# pm25.net
KiCad netlist of a schematic drawn in EAGLE
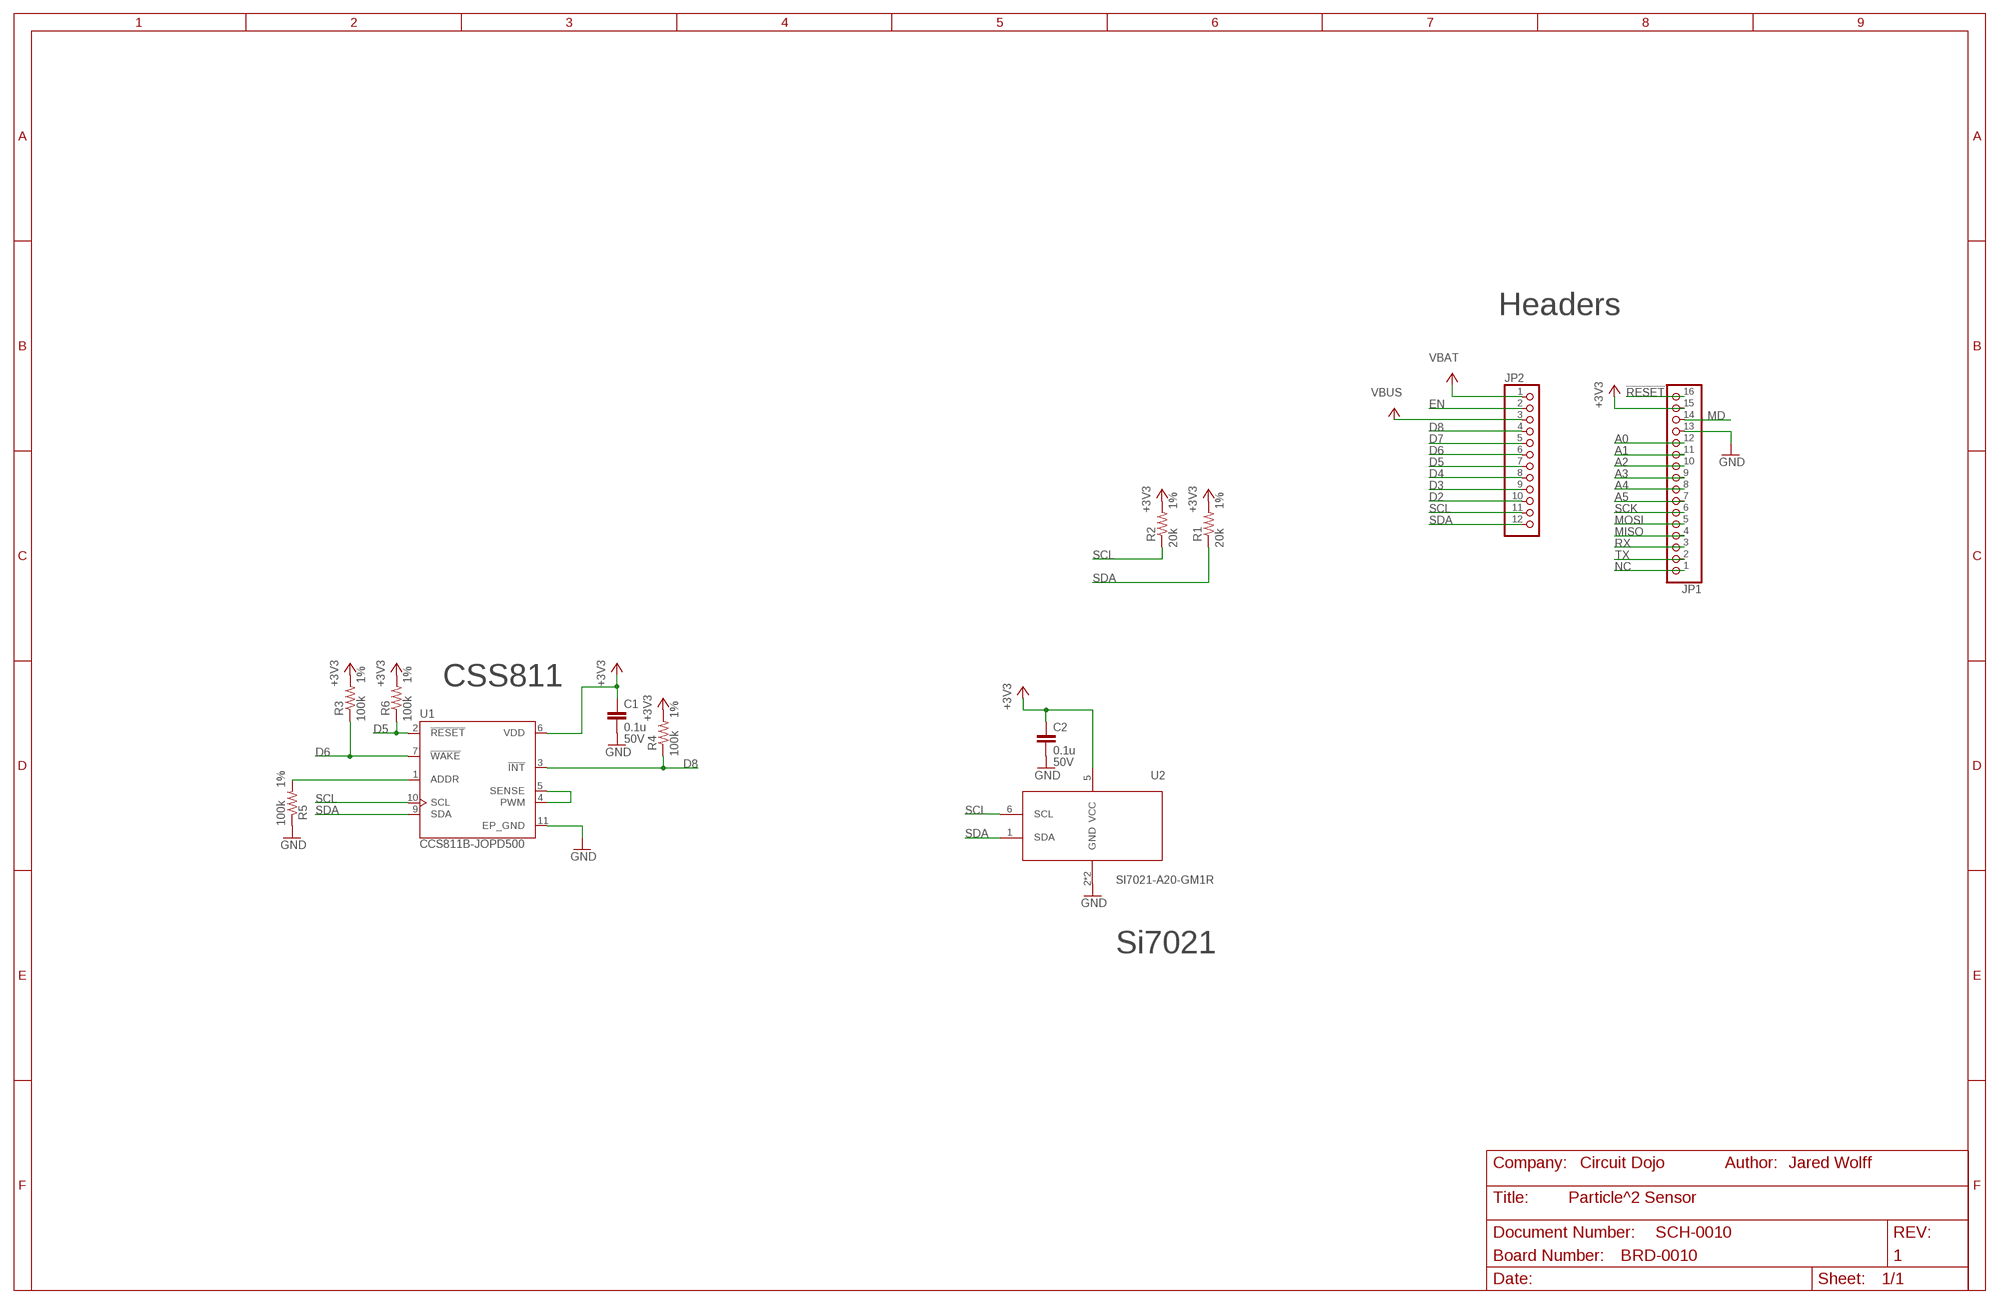
[diagram p0: schematic, sheet 1]

(export (version "E")
  (design (tool "Eeschema 10.0.6"))
  (components
    (comp (ref "C1")
      (value "0.1u")
      (footprint "eagle-import:CAPC1005X55N")
      (fields
        (field (name "VOLTHIGH") "50V")
        (field (name "MF") "Taiyo Yuden")
        (field (name "MPN") "UMK105BJ104KV-F")
      )
      (libsource (lib "eagle-import") (part "CAP-0017"))
    )
    (comp (ref "C2")
      (value "0.1u")
      (footprint "eagle-import:CAPC1005X55N")
      (fields
        (field (name "VOLTHIGH") "50V")
        (field (name "MF") "Taiyo Yuden")
        (field (name "MPN") "UMK105BJ104KV-F")
      )
      (libsource (lib "eagle-import") (part "CAP-0017"))
    )
    (comp (ref "JP1")
      (value "HEADER-1X16ROUND")
      (footprint "eagle-import:1X16_ROUND")
      (fields (field (name "MPN") "PPPC161LFBN-RC"))
      (libsource (lib "eagle-import") (part "HEADER-1X16ROUND"))
    )
    (comp (ref "JP2")
      (value "HEADER-1X12")
      (footprint "eagle-import:1X12_ROUND")
      (fields (field (name "MPN") "PPPC121LFBN-RC"))
      (libsource (lib "eagle-import") (part "HEADER-1X12"))
    )
    (comp (ref "R1")
      (value "20k")
      (footprint "eagle-import:R0402")
      (fields (field (name "TOLERANCE") "1%") (field (name "MPN") "RC0402FR-0720KL"))
      (libsource (lib "eagle-import") (part "RES-0054"))
    )
    (comp (ref "R2")
      (value "20k")
      (footprint "eagle-import:R0402")
      (fields (field (name "TOLERANCE") "1%") (field (name "MPN") "RC0402FR-0720KL"))
      (libsource (lib "eagle-import") (part "RES-0054"))
    )
    (comp (ref "R3")
      (value "100k")
      (footprint "eagle-import:R0402")
      (fields (field (name "TOLERANCE") "1%") (field (name "MPN") "RC0402FR07100KL"))
      (libsource (lib "eagle-import") (part "RES-0041"))
    )
    (comp (ref "R4")
      (value "100k")
      (footprint "eagle-import:R0402")
      (fields (field (name "TOLERANCE") "1%") (field (name "MPN") "RC0402FR07100KL"))
      (libsource (lib "eagle-import") (part "RES-0041"))
    )
    (comp (ref "R5")
      (value "100k")
      (footprint "eagle-import:R0402")
      (fields (field (name "TOLERANCE") "1%") (field (name "MPN") "RC0402FR07100KL"))
      (libsource (lib "eagle-import") (part "RES-0041"))
    )
    (comp (ref "R6")
      (value "100k")
      (footprint "eagle-import:R0402")
      (fields (field (name "TOLERANCE") "1%") (field (name "MPN") "RC0402FR07100KL"))
      (libsource (lib "eagle-import") (part "RES-0041"))
    )
    (comp (ref "U1")
      (value "CCS811B-JOPD500")
      (footprint "eagle-import:SON60P400X270X110-11N")
      (fields (field (name "MF") "ams"))
      (libsource (lib "eagle-import") (part "CCS811B-JOPD500"))
    )
    (comp (ref "U2")
      (value "SI7021-A20-GM1R")
      (footprint "eagle-import:SON100P300X300X80-7N")
      (fields (field (name "MPN") "SI7021-A20-GM1R"))
      (libsource (lib "eagle-import") (part "SI7021-A20-GM1R"))
    )
  )
  (nets
    (net (code "1") (name "+3V3") (class "Default")
      (node (ref "C1") (pin "1") (pinfunction "1_1") (pintype "passive"))
      (node (ref "C2") (pin "1") (pinfunction "1_1") (pintype "passive"))
      (node (ref "JP1") (pin "15") (pinfunction "15_15") (pintype "passive"))
      (node (ref "R1") (pin "2") (pinfunction "2_2") (pintype "passive"))
      (node (ref "R2") (pin "2") (pinfunction "2_2") (pintype "passive"))
      (node (ref "R3") (pin "2") (pinfunction "2_2") (pintype "passive"))
      (node (ref "R4") (pin "2") (pinfunction "2_2") (pintype "passive"))
      (node (ref "R6") (pin "2") (pinfunction "2_2") (pintype "passive"))
      (node (ref "U1") (pin "6") (pinfunction "VDD_6") (pintype "power_in"))
      (node (ref "U2") (pin "5") (pinfunction "VCC_5") (pintype "bidirectional"))
    )
    (net (code "2") (name "/A0") (class "Default")
      (node (ref "JP1") (pin "12") (pinfunction "12_12") (pintype "passive"))
    )
    (net (code "3") (name "/A1") (class "Default")
      (node (ref "JP1") (pin "11") (pinfunction "11_11") (pintype "passive"))
    )
    (net (code "4") (name "/A2") (class "Default")
      (node (ref "JP1") (pin "10") (pinfunction "10_10") (pintype "passive"))
    )
    (net (code "5") (name "/A3") (class "Default")
      (node (ref "JP1") (pin "9") (pinfunction "9_9") (pintype "passive"))
    )
    (net (code "6") (name "/A4") (class "Default")
      (node (ref "JP1") (pin "8") (pinfunction "8_8") (pintype "passive"))
    )
    (net (code "7") (name "/A5") (class "Default")
      (node (ref "JP1") (pin "7") (pinfunction "7_7") (pintype "passive"))
    )
    (net (code "8") (name "/D2") (class "Default")
      (node (ref "JP2") (pin "10") (pinfunction "10_10") (pintype "passive"))
    )
    (net (code "9") (name "/D3") (class "Default")
      (node (ref "JP2") (pin "9") (pinfunction "9_9") (pintype "passive"))
    )
    (net (code "10") (name "/D4") (class "Default")
      (node (ref "JP2") (pin "8") (pinfunction "8_8") (pintype "passive"))
    )
    (net (code "11") (name "/D5") (class "Default")
      (node (ref "JP2") (pin "7") (pinfunction "7_7") (pintype "passive"))
      (node (ref "R6") (pin "1") (pinfunction "1_1") (pintype "passive"))
      (node (ref "U1") (pin "2") (pinfunction "~{RESET}_2") (pintype "input"))
    )
    (net (code "12") (name "/D6") (class "Default")
      (node (ref "JP2") (pin "6") (pinfunction "6_6") (pintype "passive"))
      (node (ref "R3") (pin "1") (pinfunction "1_1") (pintype "passive"))
      (node (ref "U1") (pin "7") (pinfunction "~{WAKE}_7") (pintype "input"))
    )
    (net (code "13") (name "/D7") (class "Default")
      (node (ref "JP2") (pin "5") (pinfunction "5_5") (pintype "passive"))
    )
    (net (code "14") (name "/D8") (class "Default")
      (node (ref "JP2") (pin "4") (pinfunction "4_4") (pintype "passive"))
      (node (ref "R4") (pin "1") (pinfunction "1_1") (pintype "passive"))
      (node (ref "U1") (pin "3") (pinfunction "~{INT}_3") (pintype "output"))
    )
    (net (code "15") (name "/EN") (class "Default")
      (node (ref "JP2") (pin "2") (pinfunction "2_2") (pintype "passive"))
    )
    (net (code "16") (name "/MD") (class "Default")
      (node (ref "JP1") (pin "14") (pinfunction "14_14") (pintype "passive"))
    )
    (net (code "17") (name "/MISO") (class "Default")
      (node (ref "JP1") (pin "4") (pinfunction "4_4") (pintype "passive"))
    )
    (net (code "18") (name "/MOSI") (class "Default")
      (node (ref "JP1") (pin "5") (pinfunction "5_5") (pintype "passive"))
    )
    (net (code "19") (name "/NC") (class "Default")
      (node (ref "JP1") (pin "1") (pinfunction "1_1") (pintype "passive"))
    )
    (net (code "20") (name "/RX") (class "Default")
      (node (ref "JP1") (pin "3") (pinfunction "3_3") (pintype "passive"))
    )
    (net (code "21") (name "/SCK") (class "Default")
      (node (ref "JP1") (pin "6") (pinfunction "6_6") (pintype "passive"))
    )
    (net (code "22") (name "/SCL") (class "Default")
      (node (ref "JP2") (pin "11") (pinfunction "11_11") (pintype "passive"))
      (node (ref "R2") (pin "1") (pinfunction "1_1") (pintype "passive"))
      (node (ref "U1") (pin "10") (pinfunction "SCL_10") (pintype "input"))
      (node (ref "U2") (pin "6") (pinfunction "SCL_6") (pintype "bidirectional"))
    )
    (net (code "23") (name "/SDA") (class "Default")
      (node (ref "JP2") (pin "12") (pinfunction "12_12") (pintype "passive"))
      (node (ref "R1") (pin "1") (pinfunction "1_1") (pintype "passive"))
      (node (ref "U1") (pin "9") (pinfunction "SDA_9") (pintype "bidirectional"))
      (node (ref "U2") (pin "1") (pinfunction "SDA_1") (pintype "bidirectional"))
    )
    (net (code "24") (name "/TX") (class "Default")
      (node (ref "JP1") (pin "2") (pinfunction "2_2") (pintype "passive"))
    )
    (net (code "25") (name "/~{RESET}") (class "Default")
      (node (ref "JP1") (pin "16") (pinfunction "16_16") (pintype "passive"))
    )
    (net (code "26") (name "GND") (class "Default")
      (node (ref "C1") (pin "2") (pinfunction "2_2") (pintype "passive"))
      (node (ref "C2") (pin "2") (pinfunction "2_2") (pintype "passive"))
      (node (ref "JP1") (pin "13") (pinfunction "13_13") (pintype "passive"))
      (node (ref "R5") (pin "1") (pinfunction "1_1") (pintype "passive"))
      (node (ref "U1") (pin "11") (pinfunction "EP_GND_11") (pintype "power_in"))
      (node (ref "U2") (pin "2") (pinfunction "GND_2") (pintype "bidirectional"))
      (node (ref "U2") (pin "7") (pinfunction "GND_7") (pintype "bidirectional"))
    )
    (net (code "27") (name "Net-(U1-ADDR)") (class "Default")
      (node (ref "R5") (pin "2") (pinfunction "2_2") (pintype "passive"))
      (node (ref "U1") (pin "1") (pinfunction "ADDR_1") (pintype "input"))
    )
    (net (code "28") (name "Net-(U1-PWM)") (class "Default")
      (node (ref "U1") (pin "4") (pinfunction "PWM_4") (pintype "output"))
      (node (ref "U1") (pin "5") (pinfunction "SENSE_5") (pintype "output"))
    )
    (net (code "29") (name "VBAT") (class "Default")
      (node (ref "JP2") (pin "1") (pinfunction "1_1") (pintype "passive"))
    )
    (net (code "30") (name "VBUS") (class "Default")
      (node (ref "JP2") (pin "3") (pinfunction "3_3") (pintype "passive"))
    )
  )
)
